# 09-_I2C_LEDs_And_Push_Button.net
KiCad netlist of a schematic drawn in Altium Designer
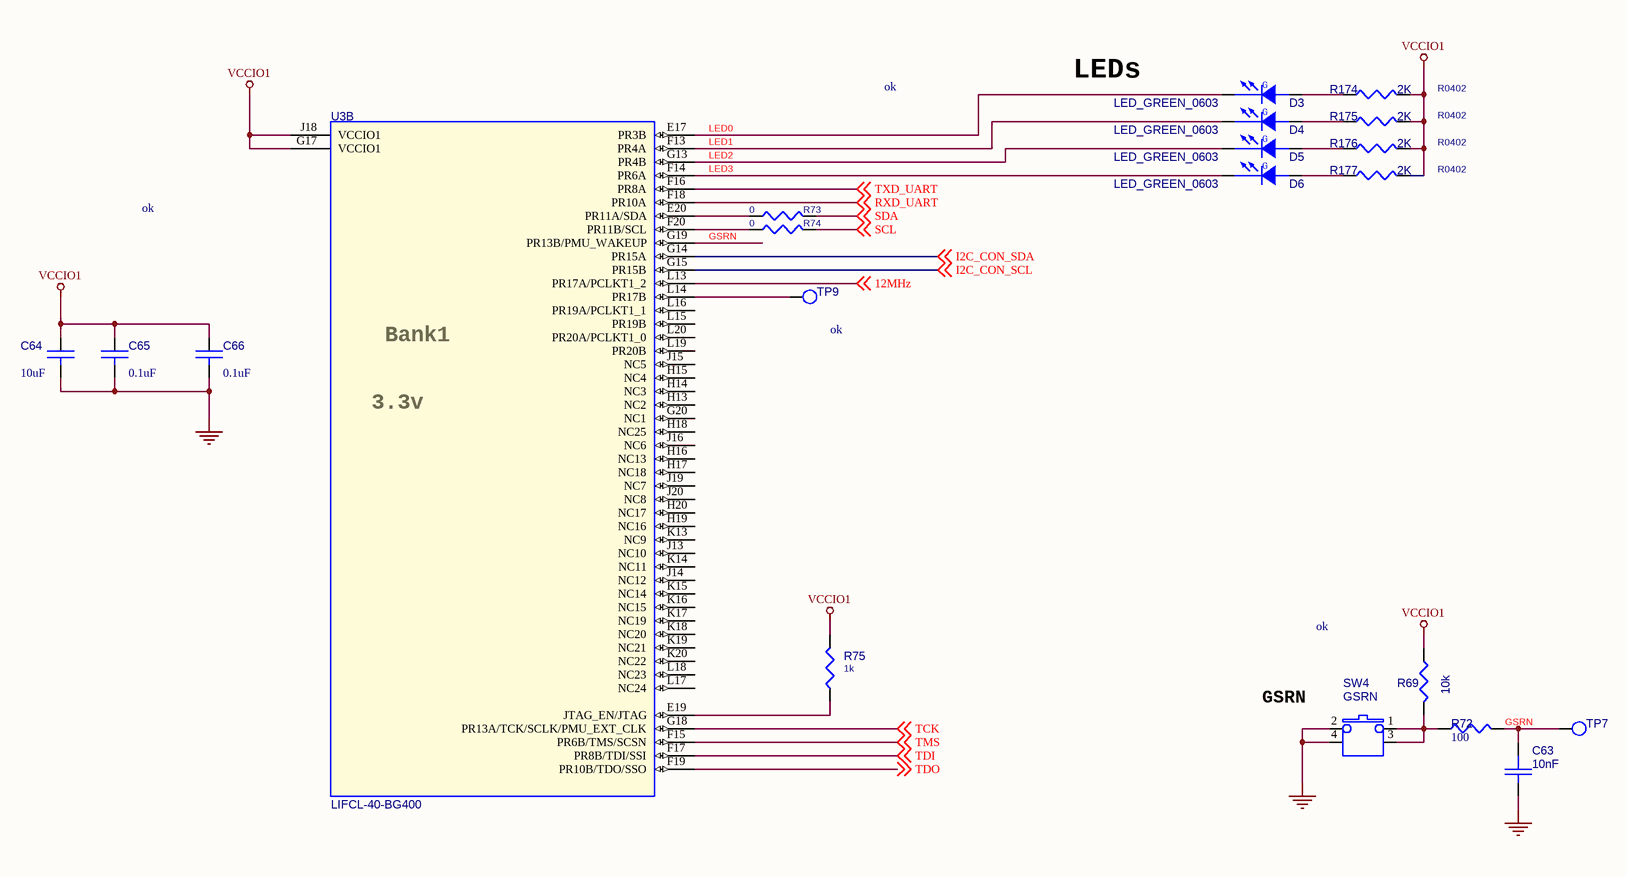
[diagram p0: 09- I2C, LEDs And Push Button.SchDoc]

(export (version "E")
  (design (tool "Eeschema 10.0.6"))
  (components
    (comp (ref "C63") (value "10nF") (footprint "RLP-130-A") (libsource (lib "*") (part "CAP_1")))
    (comp (ref "C64")
      (value "10uF")
      (footprint "C0603")
      (description "CAP CECAP CER 10UF 10V X5R 20% 0603")
      (fields
        (field (name "MANUFACTURER") "Taiyo Yuden")
        (field (name "MANUFACTURER PART NUMBER") "LMK107BJ106MALTD")
      )
      (libsource (lib "*") (part "10uF_0603"))
    )
    (comp (ref "C65")
      (value "0.1uF")
      (footprint "C0201")
      (description "CAP CER 0.1UF 25V 10% X5R 0201")
      (fields
        (field (name "MANUFACTURER") "Murata")
        (field (name "MANUFACTURER PART NUMBER") "GRM033R61E104KE14J")
      )
      (libsource (lib "*") (part "0u1_0402"))
    )
    (comp (ref "C66")
      (value "0.1uF")
      (footprint "C0201")
      (description "CAP CER 0.1UF 25V 10% X5R 0201")
      (fields
        (field (name "MANUFACTURER") "Murata")
        (field (name "MANUFACTURER PART NUMBER") "GRM033R61E104KE14J")
      )
      (libsource (lib "*") (part "0u1_0402"))
    )
    (comp (ref "D3")
      (value "LED_GREEN_0603")
      (footprint "APT1608")
      (libsource (lib "*") (part "LED-SMT1206_GREEN_1"))
    )
    (comp (ref "D4")
      (value "LED_GREEN_0603")
      (footprint "APT1608")
      (libsource (lib "*") (part "LED-SMT1206_GREEN_1"))
    )
    (comp (ref "D5")
      (value "LED_GREEN_0603")
      (footprint "APT1608")
      (libsource (lib "*") (part "LED-SMT1206_GREEN_1"))
    )
    (comp (ref "D6")
      (value "LED_GREEN_0603")
      (footprint "APT1608")
      (libsource (lib "*") (part "LED-SMT1206_GREEN_1"))
    )
    (comp (ref "R69")
      (value "10k")
      (footprint "R0402")
      (description "RES SMD 10K OHM 1% 1/16W 0402")
      (fields
        (field (name "MANUFACTURER") "Yageo")
        (field (name "MANUFACTURER PART NUMBER") "RC0402FR-0710KL")
      )
      (libsource (lib "*") (part "RES_0"))
    )
    (comp (ref "R72")
      (value "100")
      (footprint "R0402")
      (description "RES SMD 100 OHM 1% 1/16W 0402")
      (fields
        (field (name "MANUFACTURER") "Yageo")
        (field (name "MANUFACTURER PART NUMBER") "RC0402FR-07100RL")
      )
      (libsource (lib "*") (part "0R_0603"))
    )
    (comp (ref "R73")
      (value "0")
      (footprint "R0402")
      (description "RES SMD 33 OHM 1% 1/10W 0402")
      (fields
        (field (name "MANUFACTURER") "Panasonic")
        (field (name "MANUFACTURER PART NUMBER") "ERJ-2RKF33R0X")
      )
      (libsource (lib "*") (part "R_Dup3"))
    )
    (comp (ref "R74")
      (value "0")
      (footprint "R0402")
      (description "RES SMD 33 OHM 1% 1/10W 0402")
      (fields
        (field (name "MANUFACTURER") "Panasonic")
        (field (name "MANUFACTURER PART NUMBER") "ERJ-2RKF33R0X")
      )
      (libsource (lib "*") (part "R_Dup3"))
    )
    (comp (ref "R75")
      (value "1k")
      (footprint "R0402")
      (description "RES 100K OHM 1/10W 1% 0402 SMD")
      (fields (field (name "MFG") "Panasonic") (field (name "MANUFACTURER PART NUMBER") "ERJ-2RKF1003X"))
      (libsource (lib "*") (part "RES_100K_1W16_0402_5P"))
    )
    (comp (ref "R174")
      (value "2K")
      (footprint "R0402")
      (description "RES SMD 2K OHM 5% 1/10W 0402")
      (fields
        (field (name "MANUFACTURER PART NUMBER") "ERJ-2GEJ202X")
        (field (name "MFG") "Panasonic")
        (field (name "PCB FOOTPRINT") "R0402")
      )
      (libsource (lib "*") (part "RES_0"))
    )
    (comp (ref "R175")
      (value "2K")
      (footprint "R0402")
      (description "RES SMD 2K OHM 5% 1/10W 0402")
      (fields
        (field (name "MANUFACTURER PART NUMBER") "ERJ-2GEJ202X")
        (field (name "MFG") "Panasonic")
        (field (name "PCB FOOTPRINT") "R0402")
      )
      (libsource (lib "*") (part "RES_0"))
    )
    (comp (ref "R176")
      (value "2K")
      (footprint "R0402")
      (description "RES SMD 2K OHM 5% 1/10W 0402")
      (fields
        (field (name "MANUFACTURER PART NUMBER") "ERJ-2GEJ202X")
        (field (name "MFG") "Panasonic")
        (field (name "PCB FOOTPRINT") "R0402")
      )
      (libsource (lib "*") (part "RES_0"))
    )
    (comp (ref "R177")
      (value "2K")
      (footprint "R0402")
      (description "RES SMD 2K OHM 5% 1/10W 0402")
      (fields
        (field (name "MANUFACTURER PART NUMBER") "ERJ-2GEJ202X")
        (field (name "MFG") "Panasonic")
        (field (name "PCB FOOTPRINT") "R0402")
      )
      (libsource (lib "*") (part "RES_0"))
    )
    (comp (ref "SW4")
      (value "GSRN")
      (footprint "4psmd_switch")
      (description "SWITCH TACTILE SPST-NO 0.05A 12V")
      (fields (field (name "MANUFACTURER PART NUMBER") "434153017835") (field (name "MFG") "Wurth"))
      (libsource (lib "*") (part "SW PUSHBUTTON-SPST/SM"))
    )
    (comp (ref "TP7") (value "TestPoint") (footprint "TP_1MM") (libsource (lib "*") (part "T POINT R")))
    (comp (ref "TP9") (value "TestPoint") (footprint "TP_1MM") (libsource (lib "*") (part "T POINT R")))
    (comp (ref "U3")
      (value "LIFCL-40-BG400")
      (footprint "LIFCL-40-BG400")
      (libsource (lib "*") (part "LIFCL-40-BG400"))
    )
  )
  (nets
    (net (code "1") (name "/GSRN") (class "Default")
      (node (ref "C63") (pin "1") (pinfunction "1_1") (pintype "passive"))
      (node (ref "R72") (pin "2") (pinfunction "2_2") (pintype "passive"))
      (node (ref "TP7") (pin "1") (pinfunction "TP_1") (pintype "passive"))
      (node (ref "U3") (pin "G19") (pinfunction "PR13B/PMU_WAKEUP_G19") (pintype "bidirectional"))
    )
    (net (code "2") (name "/LED0") (class "Default")
      (node (ref "D3") (pin "1") (pinfunction "CATHODE_1") (pintype "passive"))
      (node (ref "U3") (pin "E17") (pinfunction "PR3B_E17") (pintype "bidirectional"))
    )
    (net (code "3") (name "/LED1") (class "Default")
      (node (ref "D4") (pin "1") (pinfunction "CATHODE_1") (pintype "passive"))
      (node (ref "U3") (pin "F13") (pinfunction "PR4A_F13") (pintype "bidirectional"))
    )
    (net (code "4") (name "/LED2") (class "Default")
      (node (ref "D5") (pin "1") (pinfunction "CATHODE_1") (pintype "passive"))
      (node (ref "U3") (pin "G13") (pinfunction "PR4B_G13") (pintype "bidirectional"))
    )
    (net (code "5") (name "/LED3") (class "Default")
      (node (ref "D6") (pin "1") (pinfunction "CATHODE_1") (pintype "passive"))
      (node (ref "U3") (pin "F14") (pinfunction "PR6A_F14") (pintype "bidirectional"))
    )
    (net (code "6") (name "12MHz") (class "Default")
      (node (ref "U3") (pin "L13") (pinfunction "PR17A/PCLKT1_2_L13") (pintype "bidirectional"))
    )
    (net (code "7") (name "GND") (class "Default")
      (node (ref "C63") (pin "2") (pinfunction "2_2") (pintype "passive"))
      (node (ref "C64") (pin "2") (pinfunction "2_2") (pintype "passive"))
      (node (ref "C65") (pin "2") (pinfunction "2_2") (pintype "passive"))
      (node (ref "C66") (pin "2") (pinfunction "2_2") (pintype "passive"))
      (node (ref "SW4") (pin "2") (pinfunction "2_2") (pintype "passive"))
      (node (ref "SW4") (pin "4") (pinfunction "4_4") (pintype "passive"))
    )
    (net (code "8") (name "I2C_CON_SCL") (class "Default")
      (node (ref "U3") (pin "G15") (pinfunction "PR15B_G15") (pintype "bidirectional"))
    )
    (net (code "9") (name "I2C_CON_SDA") (class "Default")
      (node (ref "U3") (pin "G14") (pinfunction "PR15A_G14") (pintype "bidirectional"))
    )
    (net (code "10") (name "Net-(D3-ANODE)") (class "Default")
      (node (ref "D3") (pin "2") (pinfunction "ANODE_2") (pintype "passive"))
      (node (ref "R174") (pin "1") (pinfunction "1_1") (pintype "passive"))
    )
    (net (code "11") (name "Net-(D4-ANODE)") (class "Default")
      (node (ref "D4") (pin "2") (pinfunction "ANODE_2") (pintype "passive"))
      (node (ref "R175") (pin "1") (pinfunction "1_1") (pintype "passive"))
    )
    (net (code "12") (name "Net-(D5-ANODE)") (class "Default")
      (node (ref "D5") (pin "2") (pinfunction "ANODE_2") (pintype "passive"))
      (node (ref "R176") (pin "1") (pinfunction "1_1") (pintype "passive"))
    )
    (net (code "13") (name "Net-(D6-ANODE)") (class "Default")
      (node (ref "D6") (pin "2") (pinfunction "ANODE_2") (pintype "passive"))
      (node (ref "R177") (pin "1") (pinfunction "1_1") (pintype "passive"))
    )
    (net (code "14") (name "Net-(R69-Pad2)") (class "Default")
      (node (ref "R69") (pin "2") (pinfunction "2_2") (pintype "passive"))
      (node (ref "R72") (pin "1") (pinfunction "1_1") (pintype "passive"))
      (node (ref "SW4") (pin "1") (pinfunction "1_1") (pintype "passive"))
      (node (ref "SW4") (pin "3") (pinfunction "3_3") (pintype "passive"))
    )
    (net (code "15") (name "Net-(TP9-TP)") (class "Default")
      (node (ref "TP9") (pin "1") (pinfunction "TP_1") (pintype "passive"))
      (node (ref "U3") (pin "L14") (pinfunction "PR17B_L14") (pintype "bidirectional"))
    )
    (net (code "16") (name "Net-(U3B-JTAG_EN{slash}JTAG)") (class "Default")
      (node (ref "R75") (pin "1") (pinfunction "1_1") (pintype "passive"))
      (node (ref "U3") (pin "E19") (pinfunction "JTAG_EN/JTAG_E19") (pintype "bidirectional"))
    )
    (net (code "17") (name "Net-(U3B-PR11A{slash}SDA)") (class "Default")
      (node (ref "R73") (pin "2") (pinfunction "2_2") (pintype "passive"))
      (node (ref "U3") (pin "E20") (pinfunction "PR11A/SDA_E20") (pintype "bidirectional"))
    )
    (net (code "18") (name "Net-(U3B-PR11B{slash}SCL)") (class "Default")
      (node (ref "R74") (pin "2") (pinfunction "2_2") (pintype "passive"))
      (node (ref "U3") (pin "F20") (pinfunction "PR11B/SCL_F20") (pintype "bidirectional"))
    )
    (net (code "19") (name "RXD_UART") (class "Default")
      (node (ref "U3") (pin "F18") (pinfunction "PR10A_F18") (pintype "bidirectional"))
    )
    (net (code "20") (name "SCL") (class "Default")
      (node (ref "R74") (pin "1") (pinfunction "1_1") (pintype "passive"))
    )
    (net (code "21") (name "SDA") (class "Default")
      (node (ref "R73") (pin "1") (pinfunction "1_1") (pintype "passive"))
    )
    (net (code "22") (name "TCK") (class "Default")
      (node (ref "U3") (pin "G18") (pinfunction "PR13A/TCK/SCLK/PMU_EXT_CLK_G18") (pintype "bidirectional"))
    )
    (net (code "23") (name "TDI") (class "Default")
      (node (ref "U3") (pin "F17") (pinfunction "PR8B/TDI/SSI_F17") (pintype "bidirectional"))
    )
    (net (code "24") (name "TDO") (class "Default")
      (node (ref "U3") (pin "F19") (pinfunction "PR10B/TDO/SSO_F19") (pintype "bidirectional"))
    )
    (net (code "25") (name "TMS") (class "Default")
      (node (ref "U3") (pin "F15") (pinfunction "PR6B/TMS/SCSN_F15") (pintype "bidirectional"))
    )
    (net (code "26") (name "TXD_UART") (class "Default")
      (node (ref "U3") (pin "F16") (pinfunction "PR8A_F16") (pintype "bidirectional"))
    )
    (net (code "27") (name "VCCIO1") (class "Default")
      (node (ref "C64") (pin "1") (pinfunction "1_1") (pintype "passive"))
      (node (ref "C65") (pin "1") (pinfunction "1_1") (pintype "passive"))
      (node (ref "C66") (pin "1") (pinfunction "1_1") (pintype "passive"))
      (node (ref "R174") (pin "2") (pinfunction "2_2") (pintype "passive"))
      (node (ref "R175") (pin "2") (pinfunction "2_2") (pintype "passive"))
      (node (ref "R176") (pin "2") (pinfunction "2_2") (pintype "passive"))
      (node (ref "R177") (pin "2") (pinfunction "2_2") (pintype "passive"))
      (node (ref "R69") (pin "1") (pinfunction "1_1") (pintype "passive"))
      (node (ref "R75") (pin "2") (pinfunction "2_2") (pintype "passive"))
      (node (ref "U3") (pin "G17") (pinfunction "VCCIO1_G17") (pintype "power_in"))
      (node (ref "U3") (pin "J18") (pinfunction "VCCIO1_J18") (pintype "power_in"))
    )
    (net (code "28") (name "unconnected-(U3B-NC1-PadG20)") (class "Default")
      (node (ref "U3") (pin "G20") (pinfunction "NC1_G20") (pintype "bidirectional"))
    )
    (net (code "29") (name "unconnected-(U3B-NC2-PadH13)") (class "Default")
      (node (ref "U3") (pin "H13") (pinfunction "NC2_H13") (pintype "bidirectional"))
    )
    (net (code "30") (name "unconnected-(U3B-NC3-PadH14)") (class "Default")
      (node (ref "U3") (pin "H14") (pinfunction "NC3_H14") (pintype "bidirectional"))
    )
    (net (code "31") (name "unconnected-(U3B-NC4-PadH15)") (class "Default")
      (node (ref "U3") (pin "H15") (pinfunction "NC4_H15") (pintype "bidirectional"))
    )
    (net (code "32") (name "unconnected-(U3B-NC5-PadJ15)") (class "Default")
      (node (ref "U3") (pin "J15") (pinfunction "NC5_J15") (pintype "bidirectional"))
    )
    (net (code "33") (name "unconnected-(U3B-NC6-PadJ16)") (class "Default")
      (node (ref "U3") (pin "J16") (pinfunction "NC6_J16") (pintype "bidirectional"))
    )
    (net (code "34") (name "unconnected-(U3B-NC7-PadJ19)") (class "Default")
      (node (ref "U3") (pin "J19") (pinfunction "NC7_J19") (pintype "bidirectional"))
    )
    (net (code "35") (name "unconnected-(U3B-NC8-PadJ20)") (class "Default")
      (node (ref "U3") (pin "J20") (pinfunction "NC8_J20") (pintype "bidirectional"))
    )
    (net (code "36") (name "unconnected-(U3B-NC9-PadK13)") (class "Default")
      (node (ref "U3") (pin "K13") (pinfunction "NC9_K13") (pintype "bidirectional"))
    )
    (net (code "37") (name "unconnected-(U3B-NC10-PadJ13)") (class "Default")
      (node (ref "U3") (pin "J13") (pinfunction "NC10_J13") (pintype "bidirectional"))
    )
    (net (code "38") (name "unconnected-(U3B-NC11-PadK14)") (class "Default")
      (node (ref "U3") (pin "K14") (pinfunction "NC11_K14") (pintype "bidirectional"))
    )
    (net (code "39") (name "unconnected-(U3B-NC12-PadJ14)") (class "Default")
      (node (ref "U3") (pin "J14") (pinfunction "NC12_J14") (pintype "bidirectional"))
    )
    (net (code "40") (name "unconnected-(U3B-NC13-PadH16)") (class "Default")
      (node (ref "U3") (pin "H16") (pinfunction "NC13_H16") (pintype "bidirectional"))
    )
    (net (code "41") (name "unconnected-(U3B-NC14-PadK15)") (class "Default")
      (node (ref "U3") (pin "K15") (pinfunction "NC14_K15") (pintype "bidirectional"))
    )
    (net (code "42") (name "unconnected-(U3B-NC15-PadK16)") (class "Default")
      (node (ref "U3") (pin "K16") (pinfunction "NC15_K16") (pintype "bidirectional"))
    )
    (net (code "43") (name "unconnected-(U3B-NC16-PadH19)") (class "Default")
      (node (ref "U3") (pin "H19") (pinfunction "NC16_H19") (pintype "bidirectional"))
    )
    (net (code "44") (name "unconnected-(U3B-NC17-PadH20)") (class "Default")
      (node (ref "U3") (pin "H20") (pinfunction "NC17_H20") (pintype "bidirectional"))
    )
    (net (code "45") (name "unconnected-(U3B-NC18-PadH17)") (class "Default")
      (node (ref "U3") (pin "H17") (pinfunction "NC18_H17") (pintype "bidirectional"))
    )
    (net (code "46") (name "unconnected-(U3B-NC19-PadK17)") (class "Default")
      (node (ref "U3") (pin "K17") (pinfunction "NC19_K17") (pintype "bidirectional"))
    )
    (net (code "47") (name "unconnected-(U3B-NC20-PadK18)") (class "Default")
      (node (ref "U3") (pin "K18") (pinfunction "NC20_K18") (pintype "bidirectional"))
    )
    (net (code "48") (name "unconnected-(U3B-NC21-PadK19)") (class "Default")
      (node (ref "U3") (pin "K19") (pinfunction "NC21_K19") (pintype "bidirectional"))
    )
    (net (code "49") (name "unconnected-(U3B-NC22-PadK20)") (class "Default")
      (node (ref "U3") (pin "K20") (pinfunction "NC22_K20") (pintype "bidirectional"))
    )
    (net (code "50") (name "unconnected-(U3B-NC23-PadL18)") (class "Default")
      (node (ref "U3") (pin "L18") (pinfunction "NC23_L18") (pintype "bidirectional"))
    )
    (net (code "51") (name "unconnected-(U3B-NC24-PadL17)") (class "Default")
      (node (ref "U3") (pin "L17") (pinfunction "NC24_L17") (pintype "bidirectional"))
    )
    (net (code "52") (name "unconnected-(U3B-NC25-PadH18)") (class "Default")
      (node (ref "U3") (pin "H18") (pinfunction "NC25_H18") (pintype "bidirectional"))
    )
    (net (code "53") (name "unconnected-(U3B-PR19A{slash}PCLKT1_1-PadL16)") (class "Default")
      (node (ref "U3") (pin "L16") (pinfunction "PR19A/PCLKT1_1_L16") (pintype "bidirectional"))
    )
    (net (code "54") (name "unconnected-(U3B-PR19B-PadL15)") (class "Default")
      (node (ref "U3") (pin "L15") (pinfunction "PR19B_L15") (pintype "bidirectional"))
    )
    (net (code "55") (name "unconnected-(U3B-PR20A{slash}PCLKT1_0-PadL20)") (class "Default")
      (node (ref "U3") (pin "L20") (pinfunction "PR20A/PCLKT1_0_L20") (pintype "bidirectional"))
    )
    (net (code "56") (name "unconnected-(U3B-PR20B-PadL19)") (class "Default")
      (node (ref "U3") (pin "L19") (pinfunction "PR20B_L19") (pintype "bidirectional"))
    )
  )
)
